# Power_Socket_nrf24_mini.net
KiCad netlist of a schematic drawn in EAGLE
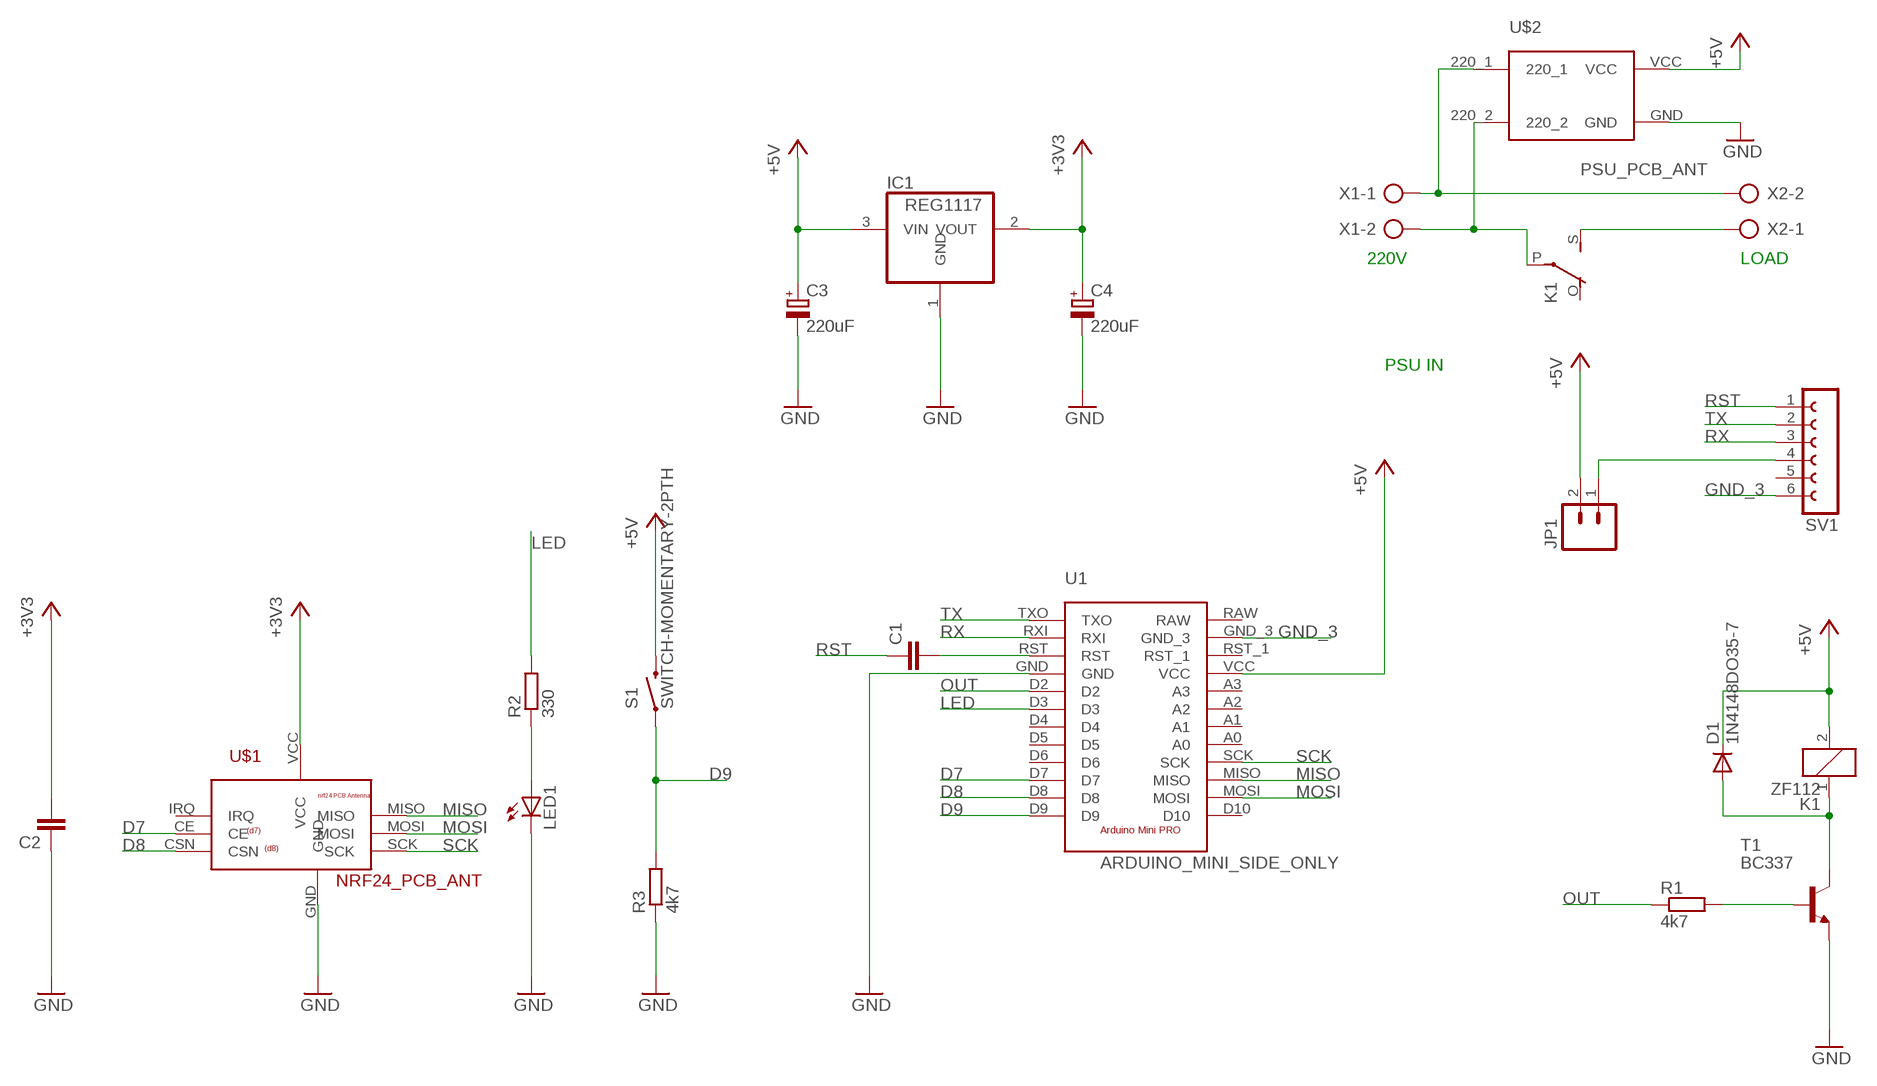
[diagram p0: schematic, sheet 1]

(export (version "E")
  (design (tool "Eeschema 10.0.6"))
  (components
    (comp (ref "C1")
      (value "C-EUC1206")
      (footprint "eagle-import:C1206")
      (libsource (lib "eagle-import") (part "C-EUC1206"))
    )
    (comp (ref "C2")
      (value "C-EUC1206")
      (footprint "eagle-import:C1206")
      (libsource (lib "eagle-import") (part "C-EUC1206"))
    )
    (comp (ref "C3")
      (value "220uF")
      (footprint "eagle-import:E2,5-6")
      (libsource (lib "eagle-import") (part "CPOL-EUE2.5-6"))
    )
    (comp (ref "C4")
      (value "220uF")
      (footprint "eagle-import:E2,5-6")
      (libsource (lib "eagle-import") (part "CPOL-EUE2.5-6"))
    )
    (comp (ref "D1")
      (value "1N4148DO35-7")
      (footprint "eagle-import:DO35-7")
      (libsource (lib "eagle-import") (part "1N4148DO35-7"))
    )
    (comp (ref "IC1")
      (value "REG1117")
      (footprint "eagle-import:SOT223")
      (libsource (lib "eagle-import") (part "REG1117"))
    )
    (comp (ref "JP1")
      (value "M02")
      (footprint "eagle-import:1X02_LONGPADS")
      (libsource (lib "eagle-import") (part "M02"))
    )
    (comp (ref "K1")
      (value "ZF112")
      (footprint "eagle-import:ZF112")
      (libsource (lib "eagle-import") (part "ZF112"))
    )
    (comp (ref "LED1")
      (value "LED3MM")
      (footprint "eagle-import:LED3MM")
      (libsource (lib "eagle-import") (part "LED3MM"))
    )
    (comp (ref "R1")
      (value "4k7")
      (footprint "eagle-import:0207_10")
      (libsource (lib "eagle-import") (part "R-EU_0207/10"))
    )
    (comp (ref "R2")
      (value "330")
      (footprint "eagle-import:0207_10")
      (libsource (lib "eagle-import") (part "R-EU_0207/10"))
    )
    (comp (ref "R3")
      (value "4k7")
      (footprint "eagle-import:0207_10")
      (libsource (lib "eagle-import") (part "R-EU_0207/10"))
    )
    (comp (ref "S1")
      (value "SWITCH-MOMENTARY-2PTH")
      (footprint "eagle-import:TACTILE-PTH")
      (libsource (lib "eagle-import") (part "SWITCH-MOMENTARY-2PTH"))
    )
    (comp (ref "SV1")
      (value "FE06-1")
      (footprint "eagle-import:FE06")
      (libsource (lib "eagle-import") (part "FE06-1"))
    )
    (comp (ref "T1")
      (value "BC337")
      (footprint "eagle-import:TO92")
      (libsource (lib "eagle-import") (part "BC337"))
    )
    (comp (ref "U$1")
      (value "NRF24_PCB_ANT")
      (footprint "eagle-import:NRF24_PCB_ANT")
      (libsource (lib "eagle-import") (part "NRF24_PCB_ANT"))
    )
    (comp (ref "U$2")
      (value "PSU_PCB_ANT")
      (footprint "eagle-import:PSU_PCB_600MA")
      (libsource (lib "eagle-import") (part "PSU_PCB_ANT"))
    )
    (comp (ref "U1")
      (value "ARDUINO_MINI_SIDE_ONLY")
      (footprint "eagle-import:ARDUINO_MINI_PRO_SIDE_ONLY")
      (libsource (lib "eagle-import") (part "ARDUINO_MINI_SIDE_ONLY"))
    )
    (comp (ref "X1")
      (value "AK300/2")
      (footprint "eagle-import:AK300_2")
      (libsource (lib "eagle-import") (part "AK300/2"))
    )
    (comp (ref "X2")
      (value "AK300/2")
      (footprint "eagle-import:AK300_2")
      (libsource (lib "eagle-import") (part "AK300/2"))
    )
  )
  (nets
    (net (code "1") (name "+3V3") (class "Default")
      (node (ref "C2") (pin "2") (pinfunction "2_2") (pintype "passive"))
      (node (ref "C4") (pin "+") (pinfunction "+_+") (pintype "passive"))
      (node (ref "IC1") (pin "2") (pinfunction "VOUT_2") (pintype "output"))
      (node (ref "U$1") (pin "VCC") (pinfunction "VCC_VCC") (pintype "bidirectional"))
    )
    (net (code "2") (name "+5V") (class "Default")
      (node (ref "C3") (pin "+") (pinfunction "+_+") (pintype "passive"))
      (node (ref "D1") (pin "C") (pinfunction "C_C") (pintype "passive"))
      (node (ref "IC1") (pin "3") (pinfunction "VIN_3") (pintype "input"))
      (node (ref "JP1") (pin "2") (pinfunction "2_2") (pintype "passive"))
      (node (ref "K1") (pin "2") (pinfunction "2_2") (pintype "passive"))
      (node (ref "S1") (pin "3") (pinfunction "2_3") (pintype "passive"))
      (node (ref "U$2") (pin "VCC") (pinfunction "VCC_VCC") (pintype "bidirectional"))
      (node (ref "U1") (pin "VCC") (pinfunction "VCC_VCC") (pintype "bidirectional"))
    )
    (net (code "3") (name "/D7") (class "Default")
      (node (ref "U$1") (pin "CE") (pinfunction "CE_CE") (pintype "bidirectional"))
      (node (ref "U1") (pin "D7") (pinfunction "D7_D7") (pintype "bidirectional"))
    )
    (net (code "4") (name "/D8") (class "Default")
      (node (ref "U$1") (pin "CSN") (pinfunction "CSN_CSN") (pintype "bidirectional"))
      (node (ref "U1") (pin "D8") (pinfunction "D8_D8") (pintype "bidirectional"))
    )
    (net (code "5") (name "/D9") (class "Default")
      (node (ref "R3") (pin "2") (pinfunction "2_2") (pintype "passive"))
      (node (ref "S1") (pin "1") (pinfunction "1_1") (pintype "passive"))
      (node (ref "U1") (pin "D9") (pinfunction "D9_D9") (pintype "bidirectional"))
    )
    (net (code "6") (name "/GND_3") (class "Default")
      (node (ref "SV1") (pin "6") (pinfunction "6_6") (pintype "passive"))
      (node (ref "U1") (pin "GND_3") (pinfunction "GND_3_GND_3") (pintype "bidirectional"))
    )
    (net (code "7") (name "/LED") (class "Default")
      (node (ref "R2") (pin "2") (pinfunction "2_2") (pintype "passive"))
      (node (ref "U1") (pin "D3") (pinfunction "D3_D3") (pintype "bidirectional"))
    )
    (net (code "8") (name "/MISO") (class "Default")
      (node (ref "U$1") (pin "MISO") (pinfunction "MISO_MISO") (pintype "bidirectional"))
      (node (ref "U1") (pin "MISO") (pinfunction "MISO_MISO") (pintype "bidirectional"))
    )
    (net (code "9") (name "/MOSI") (class "Default")
      (node (ref "U$1") (pin "MOSI") (pinfunction "MOSI_MOSI") (pintype "bidirectional"))
      (node (ref "U1") (pin "MOSI") (pinfunction "MOSI_MOSI") (pintype "bidirectional"))
    )
    (net (code "10") (name "/OUT") (class "Default")
      (node (ref "R1") (pin "1") (pinfunction "1_1") (pintype "passive"))
      (node (ref "U1") (pin "D2") (pinfunction "D2_D2") (pintype "bidirectional"))
    )
    (net (code "11") (name "/RST") (class "Default")
      (node (ref "C1") (pin "1") (pinfunction "1_1") (pintype "passive"))
      (node (ref "SV1") (pin "1") (pinfunction "1_1") (pintype "passive"))
    )
    (net (code "12") (name "/RX") (class "Default")
      (node (ref "SV1") (pin "3") (pinfunction "3_3") (pintype "passive"))
      (node (ref "U1") (pin "RXI") (pinfunction "RXI_RXI") (pintype "bidirectional"))
    )
    (net (code "13") (name "/SCK") (class "Default")
      (node (ref "U$1") (pin "SCK") (pinfunction "SCK_SCK") (pintype "bidirectional"))
      (node (ref "U1") (pin "SCK") (pinfunction "SCK_SCK") (pintype "bidirectional"))
    )
    (net (code "14") (name "/TX") (class "Default")
      (node (ref "SV1") (pin "2") (pinfunction "2_2") (pintype "passive"))
      (node (ref "U1") (pin "TXO") (pinfunction "TXO_TXO") (pintype "bidirectional"))
    )
    (net (code "15") (name "GND") (class "Default")
      (node (ref "C2") (pin "1") (pinfunction "1_1") (pintype "passive"))
      (node (ref "C3") (pin "-") (pinfunction "-_-") (pintype "passive"))
      (node (ref "C4") (pin "-") (pinfunction "-_-") (pintype "passive"))
      (node (ref "IC1") (pin "1") (pinfunction "GND_1") (pintype "power_in"))
      (node (ref "LED1") (pin "K") (pinfunction "C_K") (pintype "passive"))
      (node (ref "R3") (pin "1") (pinfunction "1_1") (pintype "passive"))
      (node (ref "T1") (pin "1") (pinfunction "E_1") (pintype "passive"))
      (node (ref "U$1") (pin "GND") (pinfunction "GND_GND") (pintype "bidirectional"))
      (node (ref "U$2") (pin "GND") (pinfunction "GND_GND") (pintype "bidirectional"))
      (node (ref "U1") (pin "GND") (pinfunction "GND_GND") (pintype "bidirectional"))
    )
    (net (code "16") (name "Net-(C1-Pad2)") (class "Default")
      (node (ref "C1") (pin "2") (pinfunction "2_2") (pintype "passive"))
      (node (ref "U1") (pin "RST") (pinfunction "RST_RST") (pintype "bidirectional"))
    )
    (net (code "17") (name "Net-(JP1-Pad1)") (class "Default")
      (node (ref "JP1") (pin "1") (pinfunction "1_1") (pintype "passive"))
      (node (ref "SV1") (pin "4") (pinfunction "4_4") (pintype "passive"))
    )
    (net (code "18") (name "Net-(LED1-PadA)") (class "Default")
      (node (ref "LED1") (pin "A") (pinfunction "A_A") (pintype "passive"))
      (node (ref "R2") (pin "1") (pinfunction "1_1") (pintype "passive"))
    )
    (net (code "19") (name "Net-(T1-B)") (class "Default")
      (node (ref "R1") (pin "2") (pinfunction "2_2") (pintype "passive"))
      (node (ref "T1") (pin "2") (pinfunction "B_2") (pintype "passive"))
    )
    (net (code "20") (name "Net-(T1-C)") (class "Default")
      (node (ref "D1") (pin "A") (pinfunction "A_A") (pintype "passive"))
      (node (ref "K1") (pin "1") (pinfunction "1_1") (pintype "passive"))
      (node (ref "T1") (pin "3") (pinfunction "C_3") (pintype "passive"))
    )
    (net (code "21") (name "Net-(X1A-KL)") (class "Default")
      (node (ref "U$2") (pin "220_1") (pinfunction "220_1_220_1") (pintype "bidirectional"))
      (node (ref "X1") (pin "1") (pinfunction "KL_1") (pintype "passive"))
      (node (ref "X2") (pin "2") (pinfunction "KL_2") (pintype "passive"))
    )
    (net (code "22") (name "Net-(X1B-KL)") (class "Default")
      (node (ref "K1") (pin "P") (pinfunction "P_P") (pintype "passive"))
      (node (ref "U$2") (pin "220_2") (pinfunction "220_2_220_2") (pintype "bidirectional"))
      (node (ref "X1") (pin "2") (pinfunction "KL_2") (pintype "passive"))
    )
    (net (code "23") (name "Net-(X2A-KL)") (class "Default")
      (node (ref "K1") (pin "S") (pinfunction "S_S") (pintype "passive"))
      (node (ref "X2") (pin "1") (pinfunction "KL_1") (pintype "passive"))
    )
    (net (code "24") (name "unconnected-(K1-PadO)") (class "Default")
      (node (ref "K1") (pin "O") (pinfunction "O_O") (pintype "passive"))
    )
    (net (code "25") (name "unconnected-(SV1-Pad5)") (class "Default")
      (node (ref "SV1") (pin "5") (pinfunction "5_5") (pintype "passive"))
    )
    (net (code "26") (name "unconnected-(U$1-PadIRQ)") (class "Default")
      (node (ref "U$1") (pin "IRQ") (pinfunction "IRQ_IRQ") (pintype "bidirectional"))
    )
    (net (code "27") (name "unconnected-(U1-PadA0)") (class "Default")
      (node (ref "U1") (pin "A0") (pinfunction "A0_A0") (pintype "bidirectional"))
    )
    (net (code "28") (name "unconnected-(U1-PadA1)") (class "Default")
      (node (ref "U1") (pin "A1") (pinfunction "A1_A1") (pintype "bidirectional"))
    )
    (net (code "29") (name "unconnected-(U1-PadA2)") (class "Default")
      (node (ref "U1") (pin "A2") (pinfunction "A2_A2") (pintype "bidirectional"))
    )
    (net (code "30") (name "unconnected-(U1-PadA3)") (class "Default")
      (node (ref "U1") (pin "A3") (pinfunction "A3_A3") (pintype "bidirectional"))
    )
    (net (code "31") (name "unconnected-(U1-PadD4)") (class "Default")
      (node (ref "U1") (pin "D4") (pinfunction "D4_D4") (pintype "bidirectional"))
    )
    (net (code "32") (name "unconnected-(U1-PadD5)") (class "Default")
      (node (ref "U1") (pin "D5") (pinfunction "D5_D5") (pintype "bidirectional"))
    )
    (net (code "33") (name "unconnected-(U1-PadD6)") (class "Default")
      (node (ref "U1") (pin "D6") (pinfunction "D6_D6") (pintype "bidirectional"))
    )
    (net (code "34") (name "unconnected-(U1-PadD10)") (class "Default")
      (node (ref "U1") (pin "D10") (pinfunction "D10_D10") (pintype "bidirectional"))
    )
    (net (code "35") (name "unconnected-(U1-PadRAW)") (class "Default")
      (node (ref "U1") (pin "RAW") (pinfunction "RAW_RAW") (pintype "bidirectional"))
    )
    (net (code "36") (name "unconnected-(U1-PadRST_1)") (class "Default")
      (node (ref "U1") (pin "RST_1") (pinfunction "RST_1_RST_1") (pintype "bidirectional"))
    )
  )
)
